# SCH_DIY-PICO-USB-GADGET.net
KiCad netlist of a schematic drawn in EasyEDA
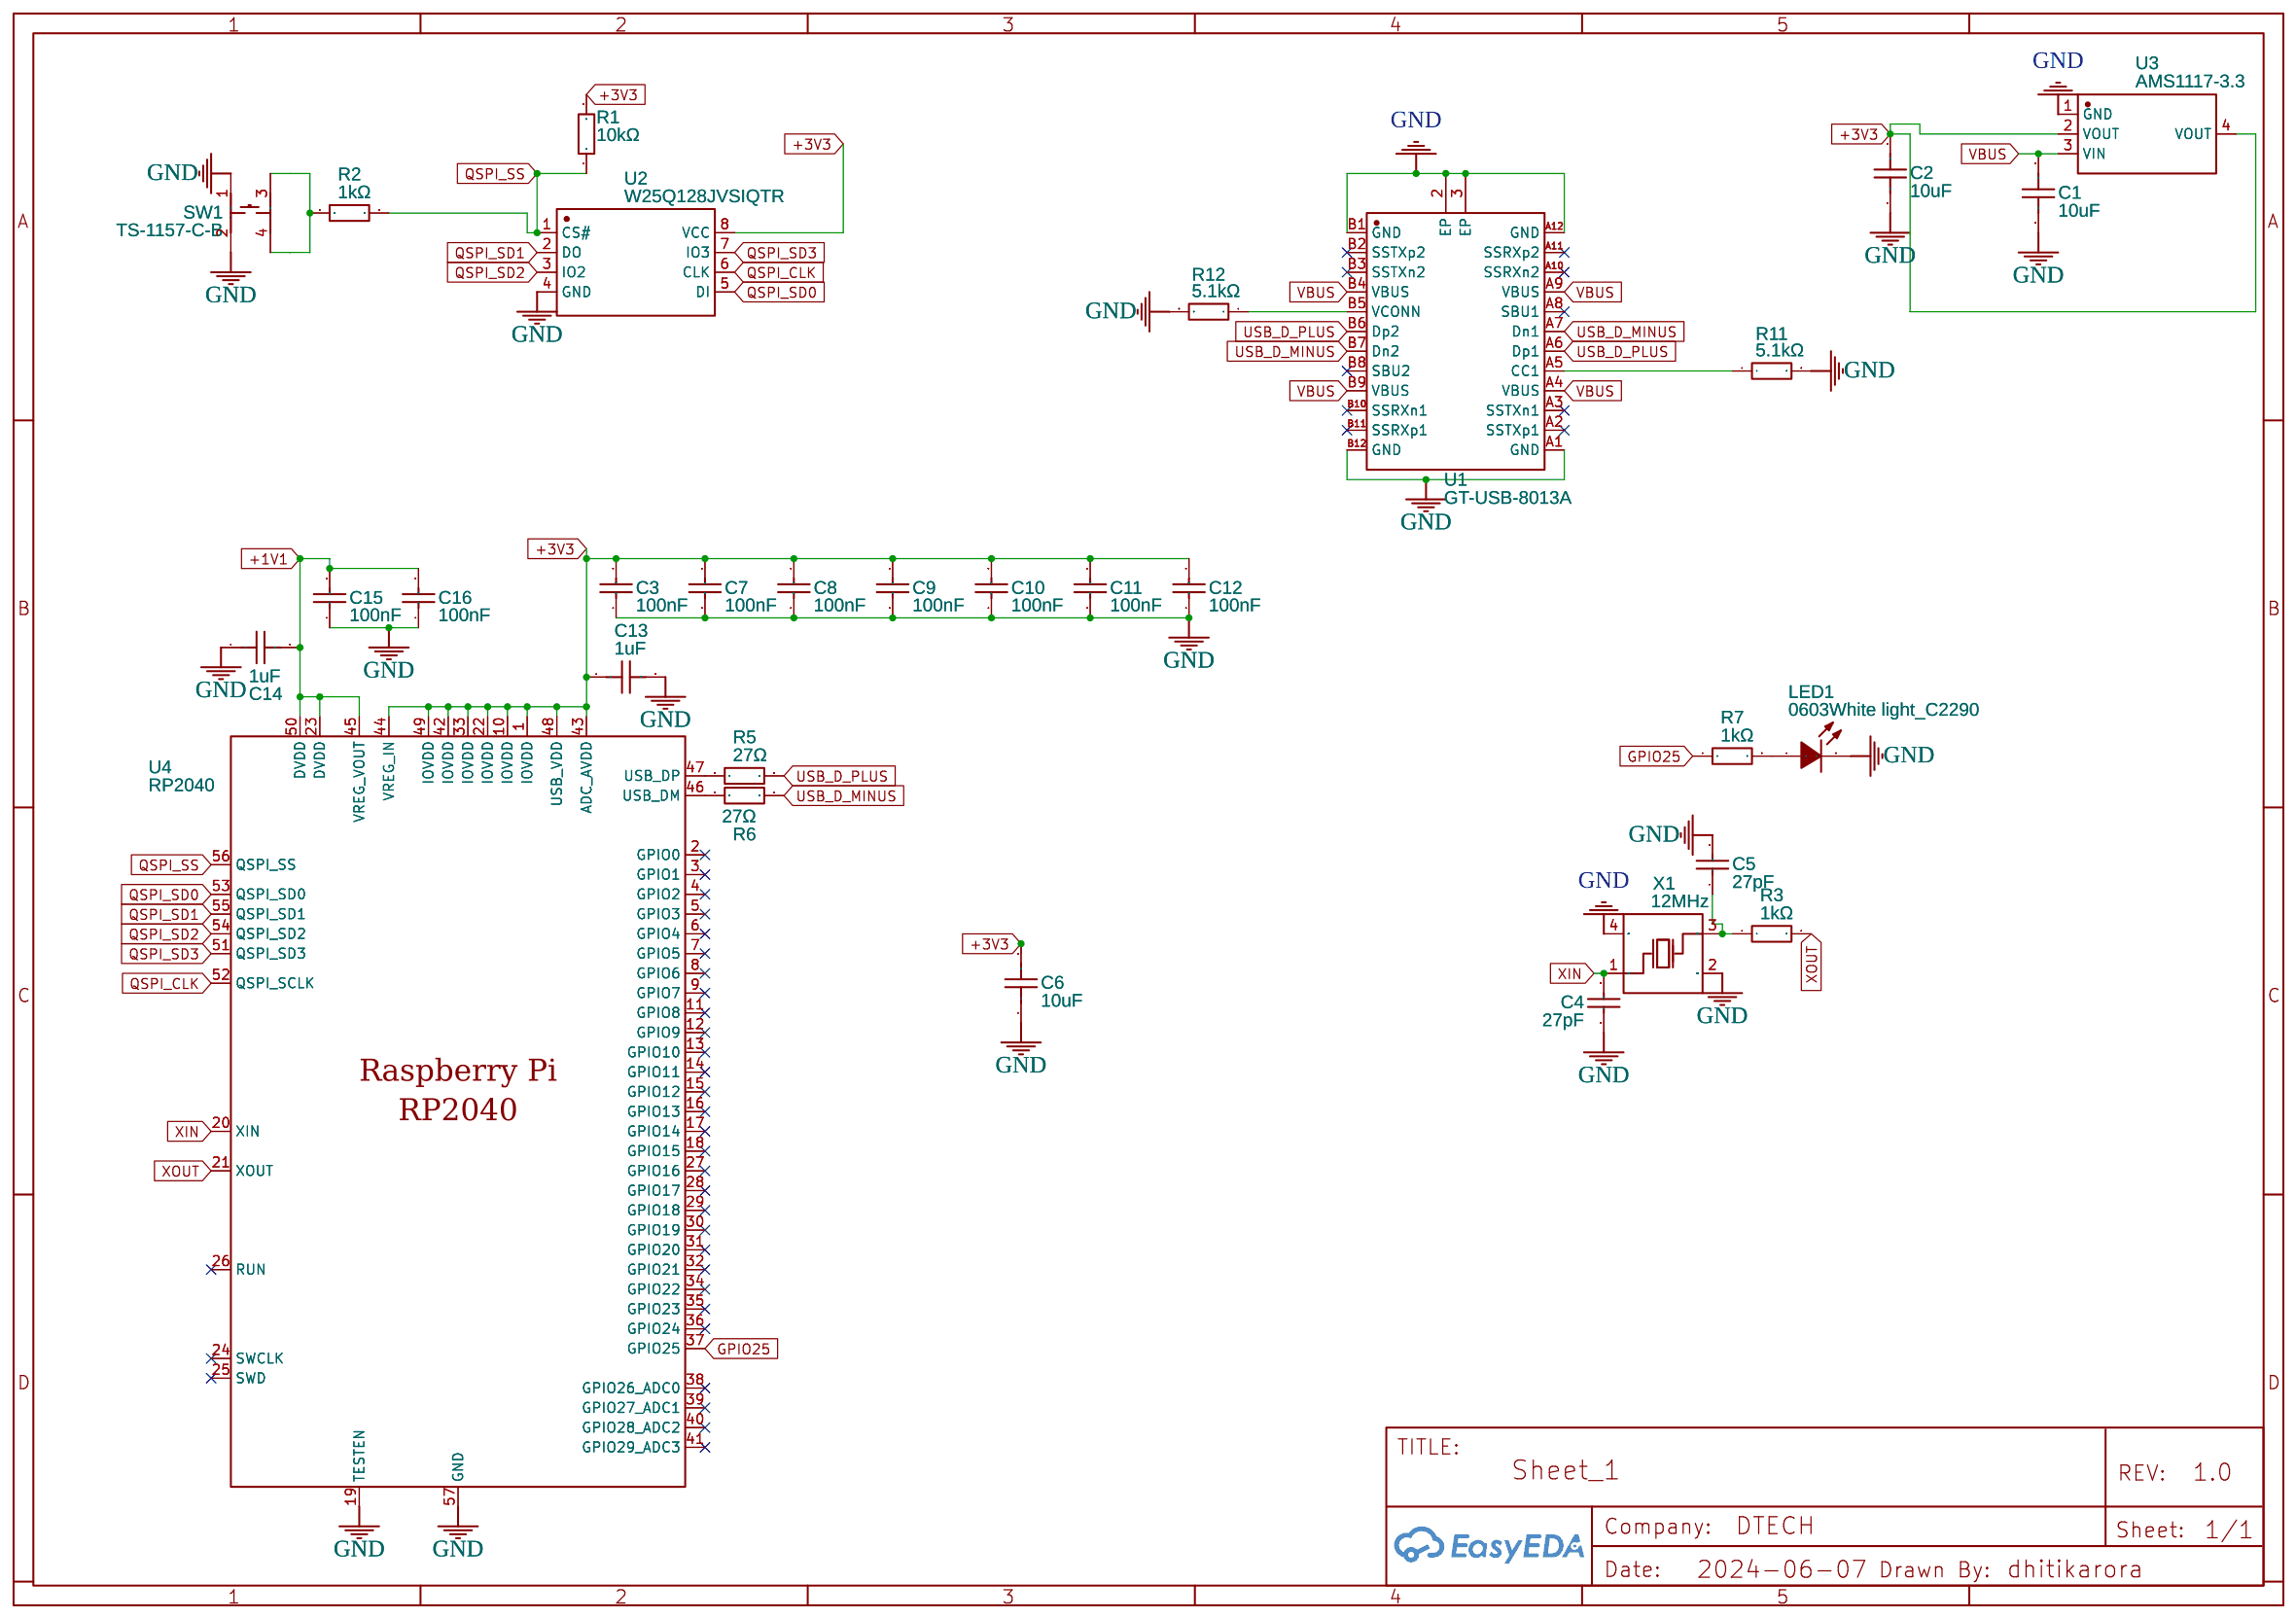
[diagram p0: schematic sheet]

(export (version "E")
  (design (tool "Eeschema 10.0.6"))
  (components
    (comp (ref "C1")
      (value "10uF")
      (fields
        (field (name "Manufacturer Part") "CL10A106KP8NNNC")
        (field (name "Manufacturer") "SAMSUNG(三星)")
      )
      (libsource (lib "") (part "CL10A106KP8NNNC"))
    )
    (comp (ref "C2")
      (value "10uF")
      (fields
        (field (name "Manufacturer Part") "CL10A106KP8NNNC")
        (field (name "Manufacturer") "SAMSUNG(三星)")
      )
      (libsource (lib "") (part "CL10A106KP8NNNC"))
    )
    (comp (ref "C3")
      (value "100nF")
      (fields
        (field (name "Manufacturer Part") "CL05B104KO5NNNC")
        (field (name "Manufacturer") "SAMSUNG(三星)")
      )
      (libsource (lib "") (part "CL05B104KO5NNNC"))
    )
    (comp (ref "C4")
      (value "27pF")
      (fields
        (field (name "Manufacturer Part") "CC0603JRNPO9BN270")
        (field (name "Manufacturer") "YAGEO(国巨)")
      )
      (libsource (lib "") (part "CC0603JRNPO9BN270"))
    )
    (comp (ref "C5")
      (value "27pF")
      (fields
        (field (name "Manufacturer Part") "CC0603JRNPO9BN270")
        (field (name "Manufacturer") "YAGEO(国巨)")
      )
      (libsource (lib "") (part "CC0603JRNPO9BN270_1"))
    )
    (comp (ref "C6")
      (value "10uF")
      (fields
        (field (name "Manufacturer Part") "CL10A106KP8NNNC")
        (field (name "Manufacturer") "SAMSUNG(三星)")
      )
      (libsource (lib "") (part "CL10A106KP8NNNC"))
    )
    (comp (ref "C7")
      (value "100nF")
      (fields
        (field (name "Manufacturer Part") "CL05B104KO5NNNC")
        (field (name "Manufacturer") "SAMSUNG(三星)")
      )
      (libsource (lib "") (part "CL05B104KO5NNNC"))
    )
    (comp (ref "C8")
      (value "100nF")
      (fields
        (field (name "Manufacturer Part") "CL05B104KO5NNNC")
        (field (name "Manufacturer") "SAMSUNG(三星)")
      )
      (libsource (lib "") (part "CL05B104KO5NNNC"))
    )
    (comp (ref "C9")
      (value "100nF")
      (fields
        (field (name "Manufacturer Part") "CL05B104KO5NNNC")
        (field (name "Manufacturer") "SAMSUNG(三星)")
      )
      (libsource (lib "") (part "CL05B104KO5NNNC"))
    )
    (comp (ref "C10")
      (value "100nF")
      (fields
        (field (name "Manufacturer Part") "CL05B104KO5NNNC")
        (field (name "Manufacturer") "SAMSUNG(三星)")
      )
      (libsource (lib "") (part "CL05B104KO5NNNC"))
    )
    (comp (ref "C11")
      (value "100nF")
      (fields
        (field (name "Manufacturer Part") "CL05B104KO5NNNC")
        (field (name "Manufacturer") "SAMSUNG(三星)")
      )
      (libsource (lib "") (part "CL05B104KO5NNNC"))
    )
    (comp (ref "C12")
      (value "100nF")
      (fields
        (field (name "Manufacturer Part") "CL05B104KO5NNNC")
        (field (name "Manufacturer") "SAMSUNG(三星)")
      )
      (libsource (lib "") (part "CL05B104KO5NNNC"))
    )
    (comp (ref "C13")
      (value "1uF")
      (fields
        (field (name "Manufacturer Part") "CL05A105KA5NQNC")
        (field (name "Manufacturer") "SAMSUNG(三星)")
      )
      (libsource (lib "") (part "CL05A105KA5NQNC_1"))
    )
    (comp (ref "C14")
      (value "1uF")
      (fields
        (field (name "Manufacturer Part") "CL05A105KA5NQNC")
        (field (name "Manufacturer") "SAMSUNG(三星)")
      )
      (libsource (lib "") (part "CL05A105KA5NQNC"))
    )
    (comp (ref "C15")
      (value "100nF")
      (fields
        (field (name "Manufacturer Part") "CL05B104KO5NNNC")
        (field (name "Manufacturer") "SAMSUNG(三星)")
      )
      (libsource (lib "") (part "CL05B104KO5NNNC"))
    )
    (comp (ref "C16")
      (value "100nF")
      (fields
        (field (name "Manufacturer Part") "CL05B104KO5NNNC")
        (field (name "Manufacturer") "SAMSUNG(三星)")
      )
      (libsource (lib "") (part "CL05B104KO5NNNC"))
    )
    (comp (ref "LED1")
      (value "0603White light_C2290")
      (fields (field (name "Manufacturer Part") "KT-0603白灯") (field (name "Manufacturer") "KENTO"))
      (libsource (lib "") (part "0603White light_C2290"))
    )
    (comp (ref "R1")
      (value "10kΩ")
      (fields
        (field (name "Manufacturer Part") "0402WGF1002TCE")
        (field (name "Manufacturer") "UNI-ROYAL(厚声)")
      )
      (libsource (lib "") (part "0402WGF1002TCE"))
    )
    (comp (ref "R2")
      (value "1kΩ")
      (fields
        (field (name "Manufacturer Part") "0402WGF1001TCE")
        (field (name "Manufacturer") "UNI-ROYAL(厚声)")
      )
      (libsource (lib "") (part "0402WGF1001TCE"))
    )
    (comp (ref "R3")
      (value "1kΩ")
      (fields
        (field (name "Manufacturer Part") "0402WGF1001TCE")
        (field (name "Manufacturer") "UNI-ROYAL(厚声)")
      )
      (libsource (lib "") (part "0402WGF1001TCE"))
    )
    (comp (ref "R5")
      (value "27Ω")
      (fields
        (field (name "Manufacturer Part") "0805W8F270JT5E")
        (field (name "Manufacturer") "UNI-ROYAL(厚声)")
      )
      (libsource (lib "") (part "0805W8F270JT5E"))
    )
    (comp (ref "R6")
      (value "27Ω")
      (fields
        (field (name "Manufacturer Part") "0805W8F270JT5E")
        (field (name "Manufacturer") "UNI-ROYAL(厚声)")
      )
      (libsource (lib "") (part "0805W8F270JT5E_1"))
    )
    (comp (ref "R7")
      (value "1kΩ")
      (fields
        (field (name "Manufacturer Part") "0402WGF1001TCE")
        (field (name "Manufacturer") "UNI-ROYAL(厚声)")
      )
      (libsource (lib "") (part "0402WGF1001TCE"))
    )
    (comp (ref "R11")
      (value "5.1kΩ")
      (fields (field (name "Manufacturer Part") "RTT02512JTH") (field (name "Manufacturer") "RALEC(旺诠)"))
      (libsource (lib "") (part "RTT02512JTH_1"))
    )
    (comp (ref "R12")
      (value "5.1kΩ")
      (fields (field (name "Manufacturer Part") "RTT02512JTH") (field (name "Manufacturer") "RALEC(旺诠)"))
      (libsource (lib "") (part "RTT02512JTH"))
    )
    (comp (ref "SW1")
      (value "TS-1157-C-B")
      (fields (field (name "Manufacturer") "XKB Connectivity(中国星坤)"))
      (libsource (lib "") (part "TS-1157-C-B"))
    )
    (comp (ref "U1")
      (value "GT-USB-8013A")
      (fields (field (name "Manufacturer") "G-Switch(品赞)"))
      (libsource (lib "") (part "GT-USB-8013A"))
    )
    (comp (ref "U2")
      (value "W25Q128JVSIQTR")
      (fields (field (name "Manufacturer Part") "W25Q128JVSIQ") (field (name "Manufacturer") "WINBOND(华邦)"))
      (libsource (lib "") (part "W25Q128JVSIQTR"))
    )
    (comp (ref "U3")
      (value "AMS1117-3.3")
      (fields (field (name "Manufacturer") "AMS"))
      (libsource (lib "") (part "AMS1117-3.3"))
    )
    (comp (ref "U4")
      (value "RP2040")
      (fields (field (name "Manufacturer") "Raspberry Pi(树莓派)"))
      (libsource (lib "") (part "RP2040"))
    )
    (comp (ref "X1")
      (value "12MHz")
      (fields (field (name "Manufacturer Part") "X322512MSB4SI") (field (name "Manufacturer") "YXC(扬兴晶振)"))
      (libsource (lib "") (part "X322512MSB4SI"))
    )
  )
  (nets
    (net (code "1") (name "+1V1") (class "Default")
      (node (ref "C14") (pin "2") (pinfunction "2_2") (pintype "unspecified"))
      (node (ref "C15") (pin "2") (pinfunction "2_2") (pintype "input"))
      (node (ref "C16") (pin "2") (pinfunction "2_2") (pintype "input"))
      (node (ref "U4") (pin "23") (pinfunction "DVDD_23") (pintype "bidirectional"))
      (node (ref "U4") (pin "45") (pinfunction "VREG_VOUT_45") (pintype "bidirectional"))
      (node (ref "U4") (pin "50") (pinfunction "DVDD_50") (pintype "bidirectional"))
    )
    (net (code "2") (name "+3V3") (class "Default")
      (node (ref "C10") (pin "2") (pinfunction "2_2") (pintype "input"))
      (node (ref "C11") (pin "2") (pinfunction "2_2") (pintype "input"))
      (node (ref "C12") (pin "2") (pinfunction "2_2") (pintype "input"))
      (node (ref "C13") (pin "1") (pinfunction "1_1") (pintype "unspecified"))
      (node (ref "C2") (pin "2") (pinfunction "2_2") (pintype "unspecified"))
      (node (ref "C3") (pin "2") (pinfunction "2_2") (pintype "input"))
      (node (ref "C6") (pin "2") (pinfunction "2_2") (pintype "unspecified"))
      (node (ref "C7") (pin "2") (pinfunction "2_2") (pintype "input"))
      (node (ref "C8") (pin "2") (pinfunction "2_2") (pintype "input"))
      (node (ref "C9") (pin "2") (pinfunction "2_2") (pintype "input"))
      (node (ref "R1") (pin "2") (pinfunction "2_2") (pintype "input"))
      (node (ref "U2") (pin "8") (pinfunction "VCC_8") (pintype "unspecified"))
      (node (ref "U3") (pin "2") (pinfunction "VOUT_2") (pintype "unspecified"))
      (node (ref "U3") (pin "4") (pinfunction "VOUT_4") (pintype "unspecified"))
      (node (ref "U4") (pin "1") (pinfunction "IOVDD_1") (pintype "bidirectional"))
      (node (ref "U4") (pin "10") (pinfunction "IOVDD_10") (pintype "bidirectional"))
      (node (ref "U4") (pin "22") (pinfunction "IOVDD_22") (pintype "bidirectional"))
      (node (ref "U4") (pin "33") (pinfunction "IOVDD_33") (pintype "bidirectional"))
      (node (ref "U4") (pin "42") (pinfunction "IOVDD_42") (pintype "bidirectional"))
      (node (ref "U4") (pin "43") (pinfunction "ADC_AVDD_43") (pintype "bidirectional"))
      (node (ref "U4") (pin "44") (pinfunction "VREG_IN_44") (pintype "bidirectional"))
      (node (ref "U4") (pin "48") (pinfunction "USB_VDD_48") (pintype "bidirectional"))
      (node (ref "U4") (pin "49") (pinfunction "IOVDD_49") (pintype "bidirectional"))
    )
    (net (code "3") (name "GND") (class "Default")
      (node (ref "C1") (pin "1") (pinfunction "1_1") (pintype "unspecified"))
      (node (ref "C10") (pin "1") (pinfunction "1_1") (pintype "input"))
      (node (ref "C11") (pin "1") (pinfunction "1_1") (pintype "input"))
      (node (ref "C12") (pin "1") (pinfunction "1_1") (pintype "input"))
      (node (ref "C13") (pin "2") (pinfunction "2_2") (pintype "unspecified"))
      (node (ref "C14") (pin "1") (pinfunction "1_1") (pintype "unspecified"))
      (node (ref "C15") (pin "1") (pinfunction "1_1") (pintype "input"))
      (node (ref "C16") (pin "1") (pinfunction "1_1") (pintype "input"))
      (node (ref "C2") (pin "1") (pinfunction "1_1") (pintype "unspecified"))
      (node (ref "C3") (pin "1") (pinfunction "1_1") (pintype "input"))
      (node (ref "C4") (pin "1") (pinfunction "1_1") (pintype "input"))
      (node (ref "C5") (pin "2") (pinfunction "2_2") (pintype "input"))
      (node (ref "C6") (pin "1") (pinfunction "1_1") (pintype "unspecified"))
      (node (ref "C7") (pin "1") (pinfunction "1_1") (pintype "input"))
      (node (ref "C8") (pin "1") (pinfunction "1_1") (pintype "input"))
      (node (ref "C9") (pin "1") (pinfunction "1_1") (pintype "input"))
      (node (ref "LED1") (pin "2") (pinfunction "K_2") (pintype "unspecified"))
      (node (ref "R11") (pin "2") (pinfunction "2_2") (pintype "input"))
      (node (ref "R12") (pin "2") (pinfunction "2_2") (pintype "input"))
      (node (ref "SW1") (pin "1") (pinfunction "1_1") (pintype "unspecified"))
      (node (ref "SW1") (pin "2") (pinfunction "2_2") (pintype "unspecified"))
      (node (ref "U1") (pin "2") (pinfunction "EP_2") (pintype "unspecified"))
      (node (ref "U1") (pin "3") (pinfunction "EP_3") (pintype "unspecified"))
      (node (ref "U1") (pin "A1") (pinfunction "GND_A1") (pintype "unspecified"))
      (node (ref "U1") (pin "A12") (pinfunction "GND_A12") (pintype "unspecified"))
      (node (ref "U1") (pin "B1") (pinfunction "GND_B1") (pintype "unspecified"))
      (node (ref "U1") (pin "B12") (pinfunction "GND_B12") (pintype "unspecified"))
      (node (ref "U2") (pin "4") (pinfunction "GND_4") (pintype "unspecified"))
      (node (ref "U3") (pin "1") (pinfunction "GND_1") (pintype "unspecified"))
      (node (ref "U4") (pin "19") (pinfunction "TESTEN_19") (pintype "unspecified"))
      (node (ref "U4") (pin "57") (pinfunction "GND_57") (pintype "bidirectional"))
      (node (ref "X1") (pin "2") (pinfunction "GND_2") (pintype "unspecified"))
      (node (ref "X1") (pin "4") (pinfunction "GND_4") (pintype "unspecified"))
    )
    (net (code "4") (name "GPIO25") (class "Default")
      (node (ref "R7") (pin "1") (pinfunction "1_1") (pintype "input"))
      (node (ref "U4") (pin "37") (pinfunction "GPIO25_37") (pintype "bidirectional"))
    )
    (net (code "5") (name "Net-(LED1-A)") (class "Default")
      (node (ref "LED1") (pin "1") (pinfunction "A_1") (pintype "unspecified"))
      (node (ref "R7") (pin "2") (pinfunction "2_2") (pintype "input"))
    )
    (net (code "6") (name "Net-(R2-Pad1)") (class "Default")
      (node (ref "R2") (pin "1") (pinfunction "1_1") (pintype "input"))
      (node (ref "SW1") (pin "3") (pinfunction "3_3") (pintype "unspecified"))
      (node (ref "SW1") (pin "4") (pinfunction "4_4") (pintype "unspecified"))
    )
    (net (code "7") (name "Net-(U1-CC1)") (class "Default")
      (node (ref "R11") (pin "1") (pinfunction "1_1") (pintype "input"))
      (node (ref "U1") (pin "A5") (pinfunction "CC1_A5") (pintype "unspecified"))
    )
    (net (code "8") (name "Net-(U1-VCONN)") (class "Default")
      (node (ref "R12") (pin "1") (pinfunction "1_1") (pintype "input"))
      (node (ref "U1") (pin "B5") (pinfunction "VCONN_B5") (pintype "unspecified"))
    )
    (net (code "9") (name "Net-(U4-USB_DM)") (class "Default")
      (node (ref "R6") (pin "2") (pinfunction "2_2") (pintype "input"))
      (node (ref "U4") (pin "46") (pinfunction "USB_DM_46") (pintype "bidirectional"))
    )
    (net (code "10") (name "Net-(U4-USB_DP)") (class "Default")
      (node (ref "R5") (pin "1") (pinfunction "1_1") (pintype "input"))
      (node (ref "U4") (pin "47") (pinfunction "USB_DP_47") (pintype "bidirectional"))
    )
    (net (code "11") (name "Net-(X1-OSC2)") (class "Default")
      (node (ref "C5") (pin "1") (pinfunction "1_1") (pintype "input"))
      (node (ref "R3") (pin "1") (pinfunction "1_1") (pintype "input"))
      (node (ref "X1") (pin "3") (pinfunction "OSC2_3") (pintype "unspecified"))
    )
    (net (code "12") (name "QSPI_CLK") (class "Default")
      (node (ref "U2") (pin "6") (pinfunction "CLK_6") (pintype "unspecified"))
      (node (ref "U4") (pin "52") (pinfunction "QSPI_SCLK_52") (pintype "output"))
    )
    (net (code "13") (name "QSPI_SD0") (class "Default")
      (node (ref "U2") (pin "5") (pinfunction "DI_5") (pintype "unspecified"))
      (node (ref "U4") (pin "53") (pinfunction "QSPI_SD0_53") (pintype "bidirectional"))
    )
    (net (code "14") (name "QSPI_SD1") (class "Default")
      (node (ref "U2") (pin "2") (pinfunction "DO_2") (pintype "unspecified"))
      (node (ref "U4") (pin "55") (pinfunction "QSPI_SD1_55") (pintype "bidirectional"))
    )
    (net (code "15") (name "QSPI_SD2") (class "Default")
      (node (ref "U2") (pin "3") (pinfunction "IO2_3") (pintype "unspecified"))
      (node (ref "U4") (pin "54") (pinfunction "QSPI_SD2_54") (pintype "bidirectional"))
    )
    (net (code "16") (name "QSPI_SD3") (class "Default")
      (node (ref "U2") (pin "7") (pinfunction "IO3_7") (pintype "unspecified"))
      (node (ref "U4") (pin "51") (pinfunction "QSPI_SD3_51") (pintype "bidirectional"))
    )
    (net (code "17") (name "QSPI_SS") (class "Default")
      (node (ref "R1") (pin "1") (pinfunction "1_1") (pintype "input"))
      (node (ref "R2") (pin "2") (pinfunction "2_2") (pintype "input"))
      (node (ref "U2") (pin "1") (pinfunction "CS#_1") (pintype "unspecified"))
      (node (ref "U4") (pin "56") (pinfunction "QSPI_SS_56") (pintype "bidirectional"))
    )
    (net (code "18") (name "USB_D_MINUS") (class "Default")
      (node (ref "R6") (pin "1") (pinfunction "1_1") (pintype "input"))
      (node (ref "U1") (pin "A7") (pinfunction "Dn1_A7") (pintype "unspecified"))
      (node (ref "U1") (pin "B7") (pinfunction "Dn2_B7") (pintype "unspecified"))
    )
    (net (code "19") (name "USB_D_PLUS") (class "Default")
      (node (ref "R5") (pin "2") (pinfunction "2_2") (pintype "input"))
      (node (ref "U1") (pin "A6") (pinfunction "Dp1_A6") (pintype "unspecified"))
      (node (ref "U1") (pin "B6") (pinfunction "Dp2_B6") (pintype "unspecified"))
    )
    (net (code "20") (name "VBUS") (class "Default")
      (node (ref "C1") (pin "2") (pinfunction "2_2") (pintype "unspecified"))
      (node (ref "U1") (pin "A4") (pinfunction "VBUS_A4") (pintype "unspecified"))
      (node (ref "U1") (pin "A9") (pinfunction "VBUS_A9") (pintype "unspecified"))
      (node (ref "U1") (pin "B4") (pinfunction "VBUS_B4") (pintype "unspecified"))
      (node (ref "U1") (pin "B9") (pinfunction "VBUS_B9") (pintype "unspecified"))
      (node (ref "U3") (pin "3") (pinfunction "VIN_3") (pintype "unspecified"))
    )
    (net (code "21") (name "XIN") (class "Default")
      (node (ref "C4") (pin "2") (pinfunction "2_2") (pintype "input"))
      (node (ref "U4") (pin "20") (pinfunction "XIN_20") (pintype "input"))
      (node (ref "X1") (pin "1") (pinfunction "OSC1_1") (pintype "unspecified"))
    )
    (net (code "22") (name "XOUT") (class "Default")
      (node (ref "R3") (pin "2") (pinfunction "2_2") (pintype "input"))
      (node (ref "U4") (pin "21") (pinfunction "XOUT_21") (pintype "unspecified"))
    )
    (net (code "23") (name "unconnected-(U1-SBU1-PadA8)") (class "Default")
      (node (ref "U1") (pin "A8") (pinfunction "SBU1_A8") (pintype "unspecified+no_connect"))
    )
    (net (code "24") (name "unconnected-(U1-SBU2-PadB8)") (class "Default")
      (node (ref "U1") (pin "B8") (pinfunction "SBU2_B8") (pintype "unspecified+no_connect"))
    )
    (net (code "25") (name "unconnected-(U1-SSRXn1-PadB10)") (class "Default")
      (node (ref "U1") (pin "B10") (pinfunction "SSRXn1_B10") (pintype "unspecified+no_connect"))
    )
    (net (code "26") (name "unconnected-(U1-SSRXn2-PadA10)") (class "Default")
      (node (ref "U1") (pin "A10") (pinfunction "SSRXn2_A10") (pintype "unspecified+no_connect"))
    )
    (net (code "27") (name "unconnected-(U1-SSRXp1-PadB11)") (class "Default")
      (node (ref "U1") (pin "B11") (pinfunction "SSRXp1_B11") (pintype "unspecified+no_connect"))
    )
    (net (code "28") (name "unconnected-(U1-SSRXp2-PadA11)") (class "Default")
      (node (ref "U1") (pin "A11") (pinfunction "SSRXp2_A11") (pintype "unspecified+no_connect"))
    )
    (net (code "29") (name "unconnected-(U1-SSTXn1-PadA3)") (class "Default")
      (node (ref "U1") (pin "A3") (pinfunction "SSTXn1_A3") (pintype "unspecified+no_connect"))
    )
    (net (code "30") (name "unconnected-(U1-SSTXn2-PadB3)") (class "Default")
      (node (ref "U1") (pin "B3") (pinfunction "SSTXn2_B3") (pintype "unspecified+no_connect"))
    )
    (net (code "31") (name "unconnected-(U1-SSTXp1-PadA2)") (class "Default")
      (node (ref "U1") (pin "A2") (pinfunction "SSTXp1_A2") (pintype "unspecified+no_connect"))
    )
    (net (code "32") (name "unconnected-(U1-SSTXp2-PadB2)") (class "Default")
      (node (ref "U1") (pin "B2") (pinfunction "SSTXp2_B2") (pintype "unspecified+no_connect"))
    )
    (net (code "33") (name "unconnected-(U4-GPIO0-Pad2)") (class "Default")
      (node (ref "U4") (pin "2") (pinfunction "GPIO0_2") (pintype "bidirectional+no_connect"))
    )
    (net (code "34") (name "unconnected-(U4-GPIO1-Pad3)") (class "Default")
      (node (ref "U4") (pin "3") (pinfunction "GPIO1_3") (pintype "bidirectional+no_connect"))
    )
    (net (code "35") (name "unconnected-(U4-GPIO2-Pad4)") (class "Default")
      (node (ref "U4") (pin "4") (pinfunction "GPIO2_4") (pintype "bidirectional+no_connect"))
    )
    (net (code "36") (name "unconnected-(U4-GPIO3-Pad5)") (class "Default")
      (node (ref "U4") (pin "5") (pinfunction "GPIO3_5") (pintype "bidirectional+no_connect"))
    )
    (net (code "37") (name "unconnected-(U4-GPIO4-Pad6)") (class "Default")
      (node (ref "U4") (pin "6") (pinfunction "GPIO4_6") (pintype "bidirectional+no_connect"))
    )
    (net (code "38") (name "unconnected-(U4-GPIO5-Pad7)") (class "Default")
      (node (ref "U4") (pin "7") (pinfunction "GPIO5_7") (pintype "bidirectional+no_connect"))
    )
    (net (code "39") (name "unconnected-(U4-GPIO6-Pad8)") (class "Default")
      (node (ref "U4") (pin "8") (pinfunction "GPIO6_8") (pintype "bidirectional+no_connect"))
    )
    (net (code "40") (name "unconnected-(U4-GPIO7-Pad9)") (class "Default")
      (node (ref "U4") (pin "9") (pinfunction "GPIO7_9") (pintype "bidirectional+no_connect"))
    )
    (net (code "41") (name "unconnected-(U4-GPIO8-Pad11)") (class "Default")
      (node (ref "U4") (pin "11") (pinfunction "GPIO8_11") (pintype "bidirectional+no_connect"))
    )
    (net (code "42") (name "unconnected-(U4-GPIO9-Pad12)") (class "Default")
      (node (ref "U4") (pin "12") (pinfunction "GPIO9_12") (pintype "bidirectional+no_connect"))
    )
    (net (code "43") (name "unconnected-(U4-GPIO10-Pad13)") (class "Default")
      (node (ref "U4") (pin "13") (pinfunction "GPIO10_13") (pintype "bidirectional+no_connect"))
    )
    (net (code "44") (name "unconnected-(U4-GPIO11-Pad14)") (class "Default")
      (node (ref "U4") (pin "14") (pinfunction "GPIO11_14") (pintype "bidirectional+no_connect"))
    )
    (net (code "45") (name "unconnected-(U4-GPIO12-Pad15)") (class "Default")
      (node (ref "U4") (pin "15") (pinfunction "GPIO12_15") (pintype "bidirectional+no_connect"))
    )
    (net (code "46") (name "unconnected-(U4-GPIO13-Pad16)") (class "Default")
      (node (ref "U4") (pin "16") (pinfunction "GPIO13_16") (pintype "bidirectional+no_connect"))
    )
    (net (code "47") (name "unconnected-(U4-GPIO14-Pad17)") (class "Default")
      (node (ref "U4") (pin "17") (pinfunction "GPIO14_17") (pintype "bidirectional+no_connect"))
    )
    (net (code "48") (name "unconnected-(U4-GPIO15-Pad18)") (class "Default")
      (node (ref "U4") (pin "18") (pinfunction "GPIO15_18") (pintype "bidirectional+no_connect"))
    )
    (net (code "49") (name "unconnected-(U4-GPIO16-Pad27)") (class "Default")
      (node (ref "U4") (pin "27") (pinfunction "GPIO16_27") (pintype "bidirectional+no_connect"))
    )
    (net (code "50") (name "unconnected-(U4-GPIO17-Pad28)") (class "Default")
      (node (ref "U4") (pin "28") (pinfunction "GPIO17_28") (pintype "bidirectional+no_connect"))
    )
    (net (code "51") (name "unconnected-(U4-GPIO18-Pad29)") (class "Default")
      (node (ref "U4") (pin "29") (pinfunction "GPIO18_29") (pintype "bidirectional+no_connect"))
    )
    (net (code "52") (name "unconnected-(U4-GPIO19-Pad30)") (class "Default")
      (node (ref "U4") (pin "30") (pinfunction "GPIO19_30") (pintype "bidirectional+no_connect"))
    )
    (net (code "53") (name "unconnected-(U4-GPIO20-Pad31)") (class "Default")
      (node (ref "U4") (pin "31") (pinfunction "GPIO20_31") (pintype "bidirectional+no_connect"))
    )
    (net (code "54") (name "unconnected-(U4-GPIO21-Pad32)") (class "Default")
      (node (ref "U4") (pin "32") (pinfunction "GPIO21_32") (pintype "bidirectional+no_connect"))
    )
    (net (code "55") (name "unconnected-(U4-GPIO22-Pad34)") (class "Default")
      (node (ref "U4") (pin "34") (pinfunction "GPIO22_34") (pintype "bidirectional+no_connect"))
    )
    (net (code "56") (name "unconnected-(U4-GPIO23-Pad35)") (class "Default")
      (node (ref "U4") (pin "35") (pinfunction "GPIO23_35") (pintype "bidirectional+no_connect"))
    )
    (net (code "57") (name "unconnected-(U4-GPIO24-Pad36)") (class "Default")
      (node (ref "U4") (pin "36") (pinfunction "GPIO24_36") (pintype "bidirectional+no_connect"))
    )
    (net (code "58") (name "unconnected-(U4-GPIO26_ADC0-Pad38)") (class "Default")
      (node (ref "U4") (pin "38") (pinfunction "GPIO26_ADC0_38") (pintype "bidirectional+no_connect"))
    )
    (net (code "59") (name "unconnected-(U4-GPIO27_ADC1-Pad39)") (class "Default")
      (node (ref "U4") (pin "39") (pinfunction "GPIO27_ADC1_39") (pintype "bidirectional+no_connect"))
    )
    (net (code "60") (name "unconnected-(U4-GPIO28_ADC2-Pad40)") (class "Default")
      (node (ref "U4") (pin "40") (pinfunction "GPIO28_ADC2_40") (pintype "bidirectional+no_connect"))
    )
    (net (code "61") (name "unconnected-(U4-GPIO29_ADC3-Pad41)") (class "Default")
      (node (ref "U4") (pin "41") (pinfunction "GPIO29_ADC3_41") (pintype "bidirectional+no_connect"))
    )
    (net (code "62") (name "unconnected-(U4-RUN-Pad26)") (class "Default")
      (node (ref "U4") (pin "26") (pinfunction "RUN_26") (pintype "input+no_connect"))
    )
    (net (code "63") (name "unconnected-(U4-SWCLK-Pad24)") (class "Default")
      (node (ref "U4") (pin "24") (pinfunction "SWCLK_24") (pintype "output+no_connect"))
    )
    (net (code "64") (name "unconnected-(U4-SWD-Pad25)") (class "Default")
      (node (ref "U4") (pin "25") (pinfunction "SWD_25") (pintype "bidirectional+no_connect"))
    )
  )
)
